# HANC_Digital_TS.net
KiCad netlist of a schematic drawn in Altium Designer
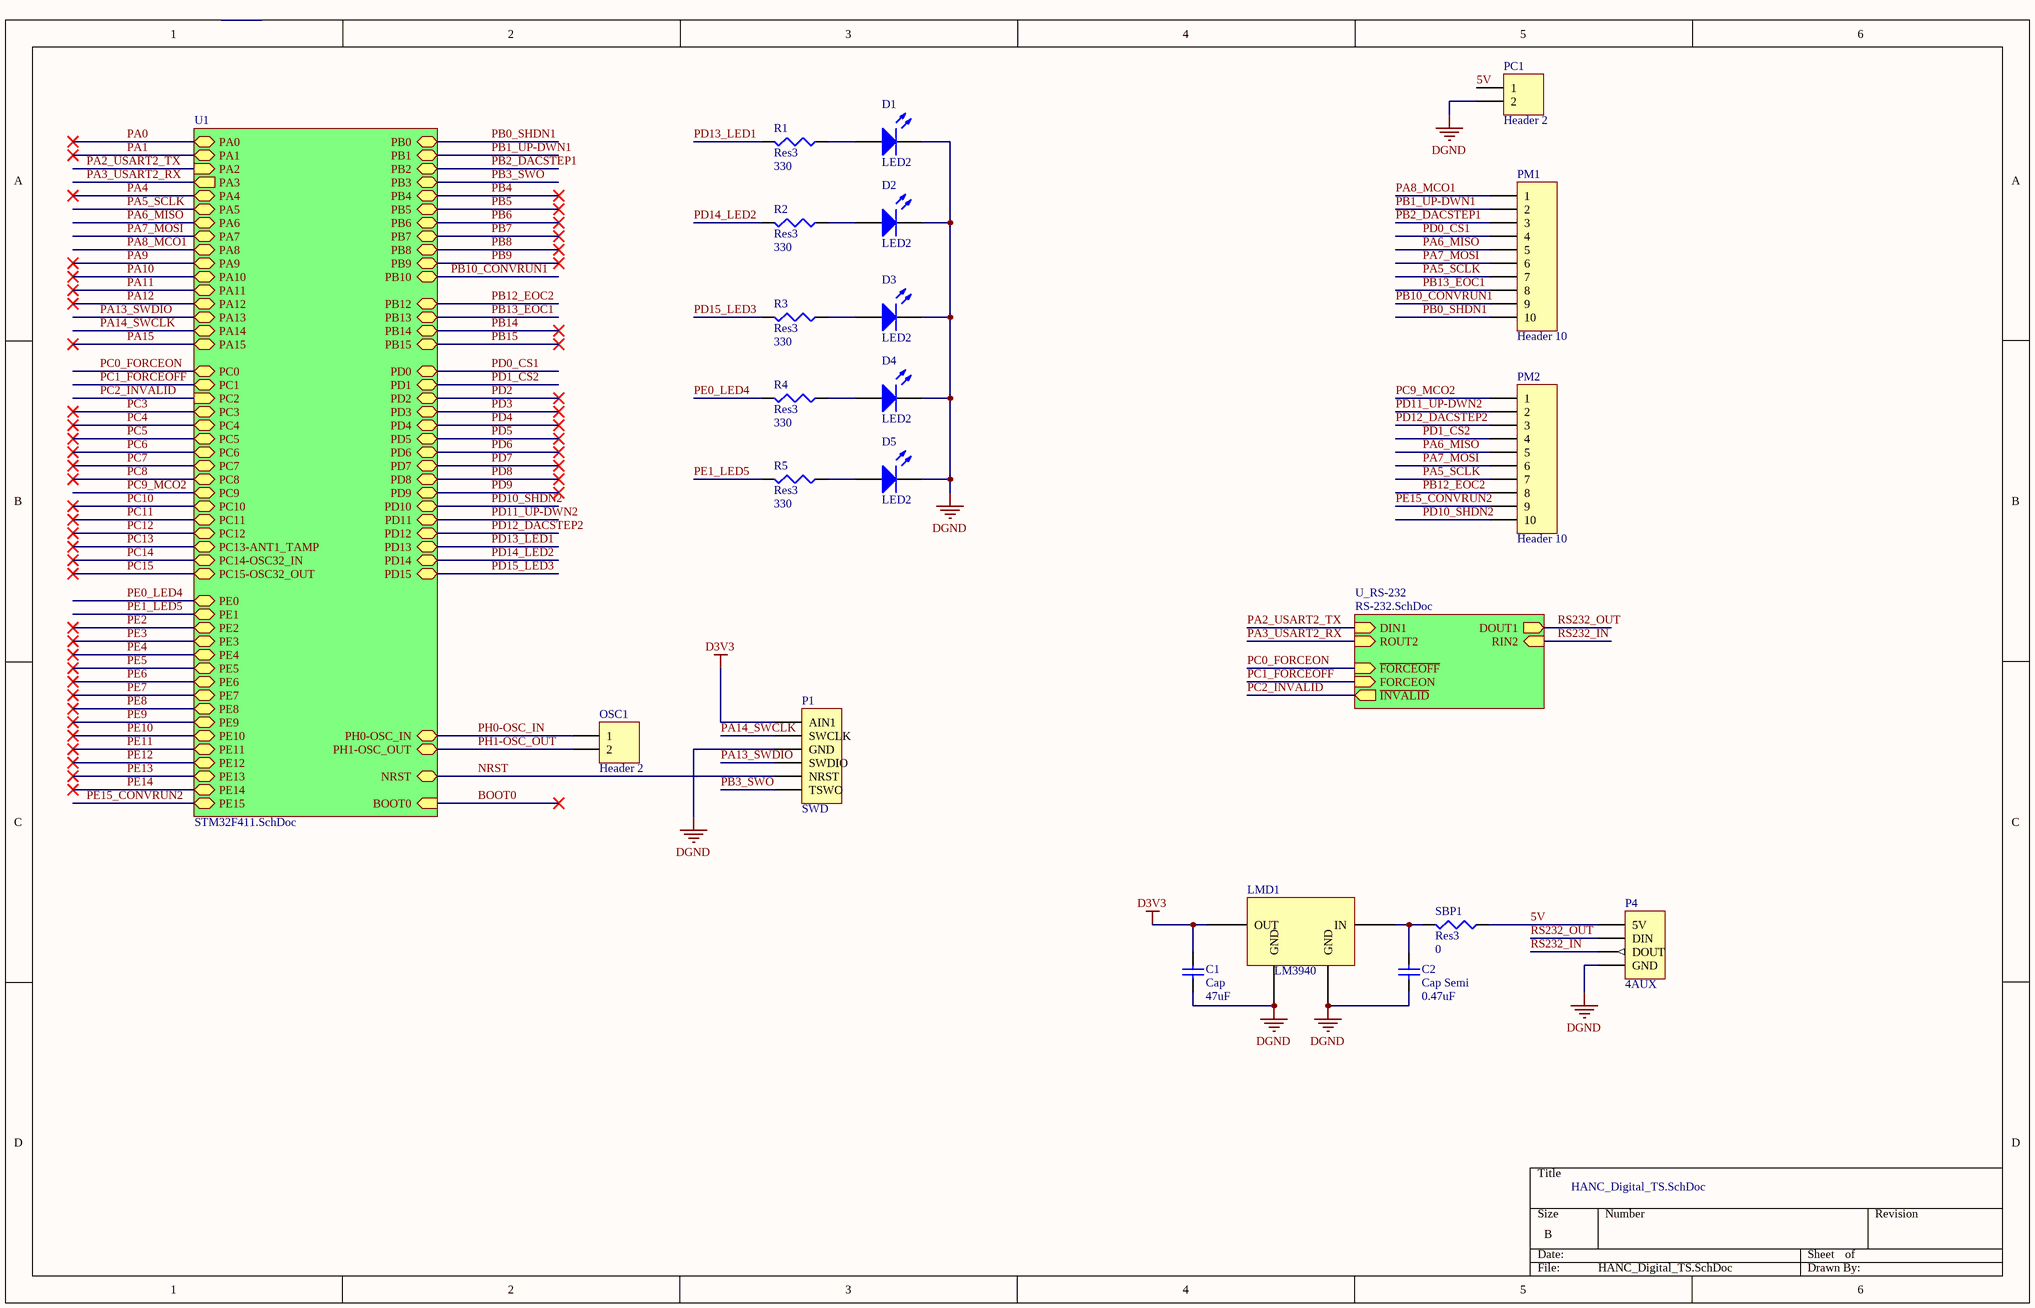
[diagram p0: HANC_Digital_TS.SchDoc]

(export (version "E")
  (design (tool "Eeschema 10.0.6"))
  (components
    (comp (ref "C1")
      (value "Cap")
      (footprint "1608[0603]")
      (description "Capacitor (Semiconductor SIM Model)")
      (fields
        (field (name "ALTIUM_VALUE") "47uF")
        (field (name "PARTNUMBER") "CL10A476MQENRBE")
        (field (name "PUBLISHER") "Altium Limited")
      )
      (libsource (lib "Miscellaneous Devices") (part "Cap Semi"))
    )
    (comp (ref "C2")
      (value "Cap Semi")
      (footprint "1608[0603]")
      (description "Capacitor (Semiconductor SIM Model)")
      (fields
        (field (name "ALTIUM_VALUE") "0.47uF")
        (field (name "PARTNUMBER") "GRM033R60J474KE90D")
        (field (name "PUBLISHER") "Altium Limited")
      )
      (libsource (lib "Miscellaneous Devices") (part "Cap Semi"))
    )
    (comp (ref "D1")
      (value "LED2")
      (footprint "3.2X1.6X1.1")
      (description "Typical RED, GREEN, YELLOW, AMBER GaAs LED")
      (fields (field (name "PARTNUMBER") "LTST-C150CKT") (field (name "PUBLISHER") "Altium Limited"))
      (libsource (lib "Miscellaneous Devices") (part "LED2"))
    )
    (comp (ref "D2")
      (value "LED2")
      (footprint "3.2X1.6X1.1")
      (description "Typical RED, GREEN, YELLOW, AMBER GaAs LED")
      (fields (field (name "PARTNUMBER") "LTST-C150CKT") (field (name "PUBLISHER") "Altium Limited"))
      (libsource (lib "Miscellaneous Devices") (part "LED2"))
    )
    (comp (ref "D3")
      (value "LED2")
      (footprint "3.2X1.6X1.1")
      (description "Typical RED, GREEN, YELLOW, AMBER GaAs LED")
      (fields (field (name "PARTNUMBER") "LTST-C150CKT") (field (name "PUBLISHER") "Altium Limited"))
      (libsource (lib "Miscellaneous Devices") (part "LED2"))
    )
    (comp (ref "D4")
      (value "LED2")
      (footprint "3.2X1.6X1.1")
      (description "Typical RED, GREEN, YELLOW, AMBER GaAs LED")
      (fields (field (name "PARTNUMBER") "LTST-C150CKT") (field (name "PUBLISHER") "Altium Limited"))
      (libsource (lib "Miscellaneous Devices") (part "LED2"))
    )
    (comp (ref "D5")
      (value "LED2")
      (footprint "3.2X1.6X1.1")
      (description "Typical RED, GREEN, YELLOW, AMBER GaAs LED")
      (fields (field (name "PARTNUMBER") "LTST-C150CKT") (field (name "PUBLISHER") "Altium Limited"))
      (libsource (lib "Miscellaneous Devices") (part "LED2"))
    )
    (comp (ref "LMD1")
      (value "LM3940")
      (footprint "SOT223_N")
      (fields (field (name "PARTNUMBER") "LM3940IMP-3.3/NOPB"))
      (libsource (lib "LN3940") (part "Component_1"))
    )
    (comp (ref "OSC1")
      (value "Header 2")
      (footprint "HDR1X2")
      (description "Header, 2-Pin")
      (fields (field (name "PUBLISHER") "Altium Limited"))
      (libsource (lib "Miscellaneous Connectors") (part "Header 2"))
    )
    (comp (ref "P1")
      (value "SWD")
      (footprint "HDR1X6")
      (description "Header, 6-Pin")
      (fields (field (name "PUBLISHER") "Altium Limited"))
      (libsource (lib "Miscellaneous Connectors") (part "Header 6"))
    )
    (comp (ref "P4")
      (value "4AUX")
      (footprint "HDR1X4")
      (description "Header, 4-Pin")
      (fields (field (name "PUBLISHER") "Altium Limited"))
      (libsource (lib "Miscellaneous Connectors") (part "Header 4"))
    )
    (comp (ref "PC1")
      (value "Header 2")
      (footprint "HDR1X2")
      (description "Header, 2-Pin")
      (fields (field (name "PUBLISHER") "Altium Limited"))
      (libsource (lib "Miscellaneous Connectors") (part "Header 2"))
    )
    (comp (ref "PM1")
      (value "Header 10")
      (footprint "HDR1X10")
      (description "Header, 10-Pin")
      (fields (field (name "PUBLISHER") "Altium Limited"))
      (libsource (lib "Miscellaneous Connectors") (part "Header 10"))
    )
    (comp (ref "PM2")
      (value "Header 10")
      (footprint "HDR1X10")
      (description "Header, 10-Pin")
      (fields (field (name "PUBLISHER") "Altium Limited"))
      (libsource (lib "Miscellaneous Connectors") (part "Header 10"))
    )
    (comp (ref "R1")
      (value "Res3")
      (footprint "0402")
      (description "Resistor")
      (fields
        (field (name "ALTIUM_VALUE") "330")
        (field (name "PARTNUMBER") "RC0402FR-07330RL")
        (field (name "PUBLISHER") "Altium Limited")
      )
      (libsource (lib "Miscellaneous Devices") (part "Res3"))
    )
    (comp (ref "R2")
      (value "Res3")
      (footprint "0402")
      (description "Resistor")
      (fields
        (field (name "ALTIUM_VALUE") "330")
        (field (name "PARTNUMBER") "RC0402FR-07330RL")
        (field (name "PUBLISHER") "Altium Limited")
      )
      (libsource (lib "Miscellaneous Devices") (part "Res3"))
    )
    (comp (ref "R3")
      (value "Res3")
      (footprint "0402")
      (description "Resistor")
      (fields
        (field (name "ALTIUM_VALUE") "330")
        (field (name "PARTNUMBER") "RC0402FR-07330RL")
        (field (name "PUBLISHER") "Altium Limited")
      )
      (libsource (lib "Miscellaneous Devices") (part "Res3"))
    )
    (comp (ref "R4")
      (value "Res3")
      (footprint "0402")
      (description "Resistor")
      (fields
        (field (name "ALTIUM_VALUE") "330")
        (field (name "PARTNUMBER") "RC0402FR-07330RL")
        (field (name "PUBLISHER") "Altium Limited")
      )
      (libsource (lib "Miscellaneous Devices") (part "Res3"))
    )
    (comp (ref "R5")
      (value "Res3")
      (footprint "0402")
      (description "Resistor")
      (fields
        (field (name "ALTIUM_VALUE") "330")
        (field (name "PARTNUMBER") "RC0402FR-07330RL")
        (field (name "PUBLISHER") "Altium Limited")
      )
      (libsource (lib "Miscellaneous Devices") (part "Res3"))
    )
    (comp (ref "SBP1")
      (value "Res3")
      (footprint "J1-0603")
      (description "Resistor")
      (fields
        (field (name "ALTIUM_VALUE") "0")
        (field (name "PARTNUMBER") "Keystone Electronics 5110")
        (field (name "PUBLISHER") "Altium Limited")
      )
      (libsource (lib "Miscellaneous Devices") (part "Res3"))
    )
  )
  (nets
    (net (code "1") (name "/5V") (class "Default")
      (node (ref "P4") (pin "1") (pinfunction "5V_1") (pintype "passive"))
      (node (ref "PC1") (pin "1") (pinfunction "1_1") (pintype "passive"))
      (node (ref "SBP1") (pin "1") (pinfunction "1_1") (pintype "passive"))
    )
    (net (code "3") (name "/NRST") (class "Default")
      (node (ref "P1") (pin "5") (pinfunction "NRST_5") (pintype "passive"))
    )
    (net (code "9") (name "/PA5_SCLK") (class "Default")
      (node (ref "PM1") (pin "7") (pinfunction "7_7") (pintype "passive"))
      (node (ref "PM2") (pin "7") (pinfunction "7_7") (pintype "passive"))
    )
    (net (code "10") (name "/PA6_MISO") (class "Default")
      (node (ref "PM1") (pin "5") (pinfunction "5_5") (pintype "passive"))
      (node (ref "PM2") (pin "5") (pinfunction "5_5") (pintype "passive"))
    )
    (net (code "11") (name "/PA7_MOSI") (class "Default")
      (node (ref "PM1") (pin "6") (pinfunction "6_6") (pintype "passive"))
      (node (ref "PM2") (pin "6") (pinfunction "6_6") (pintype "passive"))
    )
    (net (code "12") (name "/PA8_MCO1") (class "Default")
      (node (ref "PM1") (pin "1") (pinfunction "1_1") (pintype "passive"))
    )
    (net (code "17") (name "/PA13_SWDIO") (class "Default")
      (node (ref "P1") (pin "4") (pinfunction "SWDIO_4") (pintype "passive"))
    )
    (net (code "18") (name "/PA14_SWCLK") (class "Default")
      (node (ref "P1") (pin "2") (pinfunction "SWCLK_2") (pintype "passive"))
    )
    (net (code "20") (name "/PB0_SHDN1") (class "Default")
      (node (ref "PM1") (pin "10") (pinfunction "10_10") (pintype "passive"))
    )
    (net (code "21") (name "/PB1_UP-DWN1") (class "Default")
      (node (ref "PM1") (pin "2") (pinfunction "2_2") (pintype "passive"))
    )
    (net (code "22") (name "/PB2_DACSTEP1") (class "Default")
      (node (ref "PM1") (pin "3") (pinfunction "3_3") (pintype "passive"))
    )
    (net (code "23") (name "/PB3_SWO") (class "Default")
      (node (ref "P1") (pin "6") (pinfunction "TSWO_6") (pintype "passive"))
    )
    (net (code "30") (name "/PB10_CONVRUN1") (class "Default")
      (node (ref "PM1") (pin "9") (pinfunction "9_9") (pintype "passive"))
    )
    (net (code "31") (name "/PB12_EOC2") (class "Default")
      (node (ref "PM2") (pin "8") (pinfunction "8_8") (pintype "passive"))
    )
    (net (code "32") (name "/PB13_EOC1") (class "Default")
      (node (ref "PM1") (pin "8") (pinfunction "8_8") (pintype "passive"))
    )
    (net (code "44") (name "/PC9_MCO2") (class "Default")
      (node (ref "PM2") (pin "1") (pinfunction "1_1") (pintype "passive"))
    )
    (net (code "51") (name "/PD0_CS1") (class "Default")
      (node (ref "PM1") (pin "4") (pinfunction "4_4") (pintype "passive"))
    )
    (net (code "52") (name "/PD1_CS2") (class "Default")
      (node (ref "PM2") (pin "4") (pinfunction "4_4") (pintype "passive"))
    )
    (net (code "61") (name "/PD10_SHDN2") (class "Default")
      (node (ref "PM2") (pin "10") (pinfunction "10_10") (pintype "passive"))
    )
    (net (code "62") (name "/PD11_UP-DWN2") (class "Default")
      (node (ref "PM2") (pin "2") (pinfunction "2_2") (pintype "passive"))
    )
    (net (code "63") (name "/PD12_DACSTEP2") (class "Default")
      (node (ref "PM2") (pin "3") (pinfunction "3_3") (pintype "passive"))
    )
    (net (code "64") (name "/PD13_LED1") (class "Default")
      (node (ref "R1") (pin "2") (pinfunction "2_2") (pintype "passive"))
    )
    (net (code "65") (name "/PD14_LED2") (class "Default")
      (node (ref "R2") (pin "2") (pinfunction "2_2") (pintype "passive"))
    )
    (net (code "66") (name "/PD15_LED3") (class "Default")
      (node (ref "R3") (pin "2") (pinfunction "2_2") (pintype "passive"))
    )
    (net (code "67") (name "/PE0_LED4") (class "Default")
      (node (ref "R4") (pin "2") (pinfunction "2_2") (pintype "passive"))
    )
    (net (code "68") (name "/PE1_LED5") (class "Default")
      (node (ref "R5") (pin "2") (pinfunction "2_2") (pintype "passive"))
    )
    (net (code "82") (name "/PE15_CONVRUN2") (class "Default")
      (node (ref "PM2") (pin "9") (pinfunction "9_9") (pintype "passive"))
    )
    (net (code "83") (name "/PH0-OSC_IN") (class "Default")
      (node (ref "OSC1") (pin "1") (pinfunction "1_1") (pintype "passive"))
    )
    (net (code "84") (name "/PH1-OSC_OUT") (class "Default")
      (node (ref "OSC1") (pin "2") (pinfunction "2_2") (pintype "passive"))
    )
    (net (code "85") (name "/RS232_IN") (class "Default")
      (node (ref "P4") (pin "3") (pinfunction "DOUT_3") (pintype "output"))
    )
    (net (code "86") (name "/RS232_OUT") (class "Default")
      (node (ref "P4") (pin "2") (pinfunction "DIN_2") (pintype "passive"))
    )
    (net (code "87") (name "D3V3") (class "Default")
      (node (ref "C1") (pin "2") (pinfunction "2_2") (pintype "passive"))
      (node (ref "LMD1") (pin "3") (pinfunction "OUT_3") (pintype "passive"))
      (node (ref "P1") (pin "1") (pinfunction "AIN1_1") (pintype "passive"))
    )
    (net (code "88") (name "DGND") (class "Default")
      (node (ref "C1") (pin "1") (pinfunction "1_1") (pintype "passive"))
      (node (ref "C2") (pin "1") (pinfunction "1_1") (pintype "passive"))
      (node (ref "D1") (pin "2") (pinfunction "K_2") (pintype "passive"))
      (node (ref "D2") (pin "2") (pinfunction "K_2") (pintype "passive"))
      (node (ref "D3") (pin "2") (pinfunction "K_2") (pintype "passive"))
      (node (ref "D4") (pin "2") (pinfunction "K_2") (pintype "passive"))
      (node (ref "D5") (pin "2") (pinfunction "K_2") (pintype "passive"))
      (node (ref "LMD1") (pin "2") (pinfunction "GND_2") (pintype "passive"))
      (node (ref "LMD1") (pin "4") (pinfunction "GND_4") (pintype "passive"))
      (node (ref "P1") (pin "3") (pinfunction "GND_3") (pintype "passive"))
      (node (ref "P4") (pin "4") (pinfunction "GND_4") (pintype "passive"))
      (node (ref "PC1") (pin "2") (pinfunction "2_2") (pintype "passive"))
    )
    (net (code "89") (name "Net-(D1-A)") (class "Default")
      (node (ref "D1") (pin "1") (pinfunction "A_1") (pintype "passive"))
      (node (ref "R1") (pin "1") (pinfunction "1_1") (pintype "passive"))
    )
    (net (code "90") (name "Net-(D2-A)") (class "Default")
      (node (ref "D2") (pin "1") (pinfunction "A_1") (pintype "passive"))
      (node (ref "R2") (pin "1") (pinfunction "1_1") (pintype "passive"))
    )
    (net (code "91") (name "Net-(D3-A)") (class "Default")
      (node (ref "D3") (pin "1") (pinfunction "A_1") (pintype "passive"))
      (node (ref "R3") (pin "1") (pinfunction "1_1") (pintype "passive"))
    )
    (net (code "92") (name "Net-(D4-A)") (class "Default")
      (node (ref "D4") (pin "1") (pinfunction "A_1") (pintype "passive"))
      (node (ref "R4") (pin "1") (pinfunction "1_1") (pintype "passive"))
    )
    (net (code "93") (name "Net-(D5-A)") (class "Default")
      (node (ref "D5") (pin "1") (pinfunction "A_1") (pintype "passive"))
      (node (ref "R5") (pin "1") (pinfunction "1_1") (pintype "passive"))
    )
    (net (code "94") (name "Net-(LMD1-IN)") (class "Default")
      (node (ref "C2") (pin "2") (pinfunction "2_2") (pintype "passive"))
      (node (ref "LMD1") (pin "1") (pinfunction "IN_1") (pintype "passive"))
      (node (ref "SBP1") (pin "2") (pinfunction "2_2") (pintype "passive"))
    )
  )
)
